# main.net
KiCad netlist of a schematic drawn in EAGLE
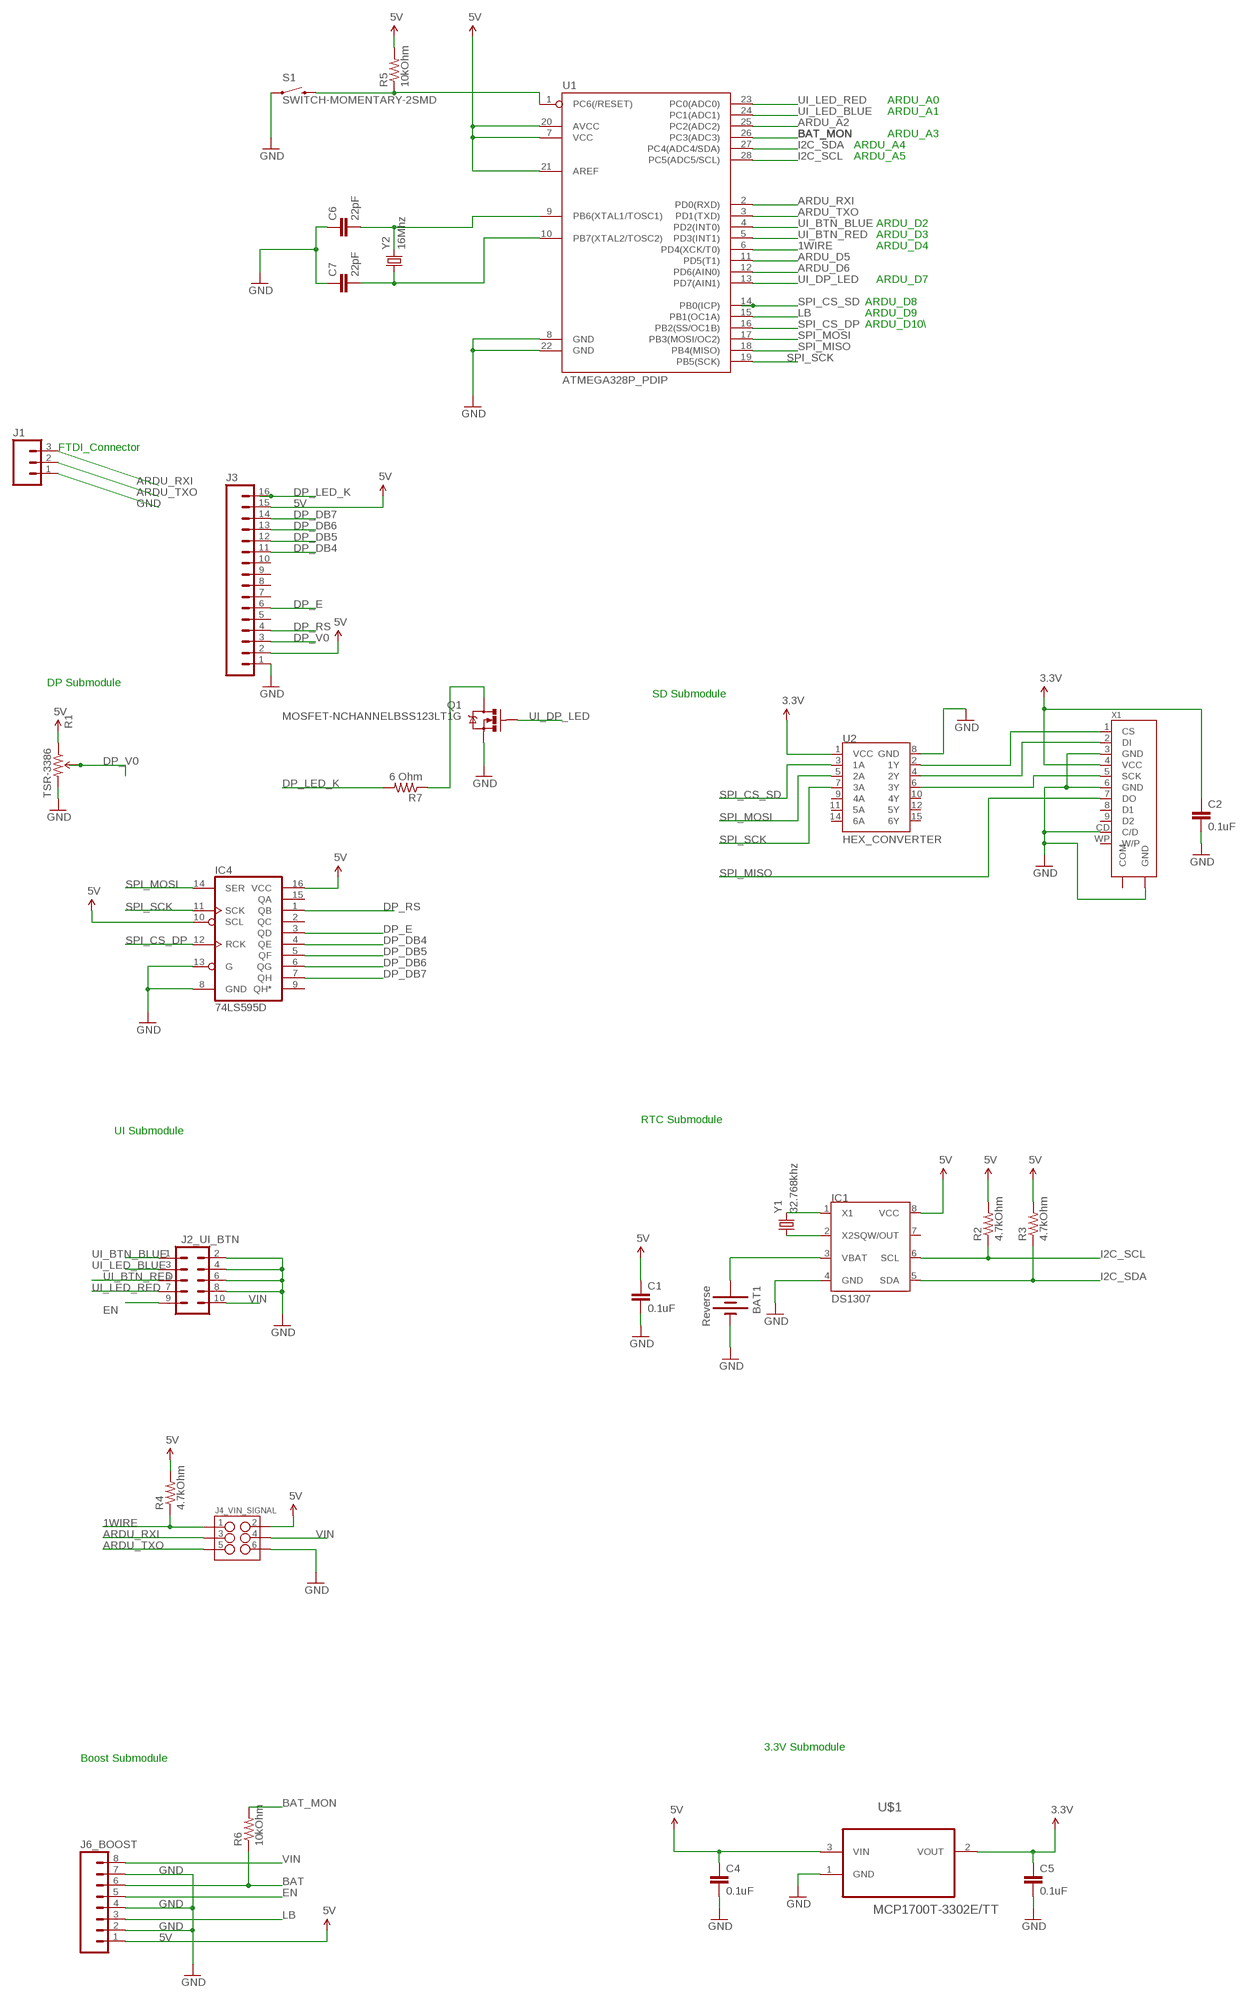
[diagram p0: schematic, sheet 1]

(export (version "E")
  (design (tool "Eeschema 10.0.6"))
  (components
    (comp (ref "BAT1")
      (value "Reverse")
      (footprint "eagle-import:BATTCOM_20MM_PTH")
      (libsource (lib "eagle-import") (part "BATTERY20PTH"))
    )
    (comp (ref "C1")
      (value "0.1uF")
      (footprint "eagle-import:1206")
      (libsource (lib "eagle-import") (part "CAP1206"))
    )
    (comp (ref "C2")
      (value "0.1uF")
      (footprint "eagle-import:1206")
      (libsource (lib "eagle-import") (part "CAP1206"))
    )
    (comp (ref "C4")
      (value "0.1uF")
      (footprint "eagle-import:1206")
      (libsource (lib "eagle-import") (part "CAP1206"))
    )
    (comp (ref "C5")
      (value "0.1uF")
      (footprint "eagle-import:1206")
      (libsource (lib "eagle-import") (part "CAP1206"))
    )
    (comp (ref "C6")
      (value "22pF")
      (footprint "eagle-import:1206")
      (libsource (lib "eagle-import") (part "CAP1206"))
    )
    (comp (ref "C7")
      (value "22pF")
      (footprint "eagle-import:1206")
      (libsource (lib "eagle-import") (part "CAP1206"))
    )
    (comp (ref "IC1")
      (value "DS1307")
      (footprint "eagle-import:SOIC-8")
      (libsource (lib "eagle-import") (part "DS1307"))
    )
    (comp (ref "IC4")
      (value "74LS595D")
      (footprint "eagle-import:SO16")
      (libsource (lib "eagle-import") (part "74595DLS"))
    )
    (comp (ref "J1")
      (value "M03LOCK")
      (footprint "eagle-import:1X03_LOCK")
      (libsource (lib "eagle-import") (part "M03LOCK"))
    )
    (comp (ref "J2_UI_BTN")
      (value "M05X2SHD")
      (footprint "eagle-import:2X5-SHROUDED")
      (libsource (lib "eagle-import") (part "M05X2SHD"))
    )
    (comp (ref "J3")
      (value "M16PTH")
      (footprint "eagle-import:1X16")
      (libsource (lib "eagle-import") (part "M16PTH"))
    )
    (comp (ref "J4_VIN_SIGNAL")
      (value "M03X2SHROUD")
      (footprint "eagle-import:2X3-SHROUDED")
      (libsource (lib "eagle-import") (part "M03X2SHROUD"))
    )
    (comp (ref "J6_BOOST")
      (value "M08")
      (footprint "eagle-import:1X08_ROUND")
      (libsource (lib "eagle-import") (part "M08"))
    )
    (comp (ref "Q1")
      (value "MOSFET-NCHANNELBSS123LT1G")
      (footprint "eagle-import:SOT23-3")
      (libsource (lib "eagle-import") (part "MOSFET-NCHANNELBSS123LT1G"))
    )
    (comp (ref "R1")
      (value "TSR-3386")
      (footprint "eagle-import:3386U")
      (libsource (lib "eagle-import") (part "TRIMPOT-PTH-KNOB"))
    )
    (comp (ref "R2")
      (value "4.7kOhm")
      (footprint "eagle-import:1206")
      (libsource (lib "eagle-import") (part "RESISTOR1206"))
    )
    (comp (ref "R3")
      (value "4.7kOhm")
      (footprint "eagle-import:1206")
      (libsource (lib "eagle-import") (part "RESISTOR1206"))
    )
    (comp (ref "R4")
      (value "4.7kOhm")
      (footprint "eagle-import:1206")
      (libsource (lib "eagle-import") (part "RESISTOR1206"))
    )
    (comp (ref "R5")
      (value "10kOhm")
      (footprint "eagle-import:1206")
      (libsource (lib "eagle-import") (part "RESISTOR1206"))
    )
    (comp (ref "R6")
      (value "10kOhm")
      (footprint "eagle-import:1206")
      (libsource (lib "eagle-import") (part "RESISTOR1206"))
    )
    (comp (ref "R7")
      (value "6 Ohm")
      (footprint "eagle-import:1206")
      (libsource (lib "eagle-import") (part "RESISTOR1206"))
    )
    (comp (ref "S1")
      (value "SWITCH-MOMENTARY-2SMD")
      (footprint "eagle-import:TACTILE-SWITCH-SMD")
      (libsource (lib "eagle-import") (part "SWITCH-MOMENTARY-2SMD"))
    )
    (comp (ref "U$1")
      (value "MCP1700T-3302E/TT")
      (footprint "eagle-import:SOT95P237X112-3N")
      (libsource (lib "eagle-import") (part "MCP1700T-3302E/TT"))
    )
    (comp (ref "U1")
      (value "ATMEGA328P_PDIP")
      (footprint "eagle-import:DIL28-3")
      (libsource (lib "eagle-import") (part "ATMEGA328P_PDIP"))
    )
    (comp (ref "U2")
      (value "HEX_CONVERTER")
      (footprint "eagle-import:SO016")
      (libsource (lib "eagle-import") (part "HEX_CONVERTER"))
    )
    (comp (ref "X1")
      (value "SD-SOCKET-AVX")
      (footprint "eagle-import:SD-SOCKET-AVX")
      (libsource (lib "eagle-import") (part "SD-SOCKET-AVX"))
    )
    (comp (ref "Y1")
      (value "32.768khz")
      (footprint "eagle-import:CRYSTAL-32KHZ-SMD-MELF")
      (libsource (lib "eagle-import") (part "CRYSTAL32-SMD-MELF"))
    )
    (comp (ref "Y2")
      (value "16Mhz")
      (footprint "eagle-import:HC49US")
      (libsource (lib "eagle-import") (part "CRYSTALHC49US"))
    )
  )
  (nets
    (net (code "1") (name "/1WIRE") (class "Default")
      (node (ref "J4_VIN_SIGNAL") (pin "1") (pinfunction "1_1") (pintype "bidirectional"))
      (node (ref "R4") (pin "1") (pinfunction "1_1") (pintype "passive"))
      (node (ref "U1") (pin "6") (pinfunction "PD4(XCK/T0)_6") (pintype "bidirectional"))
    )
    (net (code "2") (name "/ARDU_A2") (class "Default")
      (node (ref "U1") (pin "25") (pinfunction "PC2(ADC2)_25") (pintype "bidirectional"))
    )
    (net (code "3") (name "/ARDU_D5") (class "Default")
      (node (ref "U1") (pin "11") (pinfunction "PD5(T1)_11") (pintype "bidirectional"))
    )
    (net (code "4") (name "/ARDU_D6") (class "Default")
      (node (ref "U1") (pin "12") (pinfunction "PD6(AIN0)_12") (pintype "bidirectional"))
    )
    (net (code "5") (name "/ARDU_RXI") (class "Default")
      (node (ref "J1") (pin "3") (pinfunction "3_3") (pintype "passive"))
      (node (ref "J4_VIN_SIGNAL") (pin "3") (pinfunction "3_3") (pintype "bidirectional"))
      (node (ref "U1") (pin "2") (pinfunction "PD0(RXD)_2") (pintype "bidirectional"))
    )
    (net (code "6") (name "/ARDU_TXO") (class "Default")
      (node (ref "J1") (pin "2") (pinfunction "2_2") (pintype "passive"))
      (node (ref "J4_VIN_SIGNAL") (pin "5") (pinfunction "5_5") (pintype "bidirectional"))
      (node (ref "U1") (pin "3") (pinfunction "PD1(TXD)_3") (pintype "bidirectional"))
    )
    (net (code "7") (name "/BAT") (class "Default")
      (node (ref "J6_BOOST") (pin "6") (pinfunction "6_6") (pintype "passive"))
      (node (ref "R6") (pin "1") (pinfunction "1_1") (pintype "passive"))
    )
    (net (code "8") (name "/BAT_MON") (class "Default")
      (node (ref "R6") (pin "2") (pinfunction "2_2") (pintype "passive"))
      (node (ref "U1") (pin "26") (pinfunction "PC3(ADC3)_26") (pintype "bidirectional"))
    )
    (net (code "9") (name "/DP_DB4") (class "Default")
      (node (ref "IC4") (pin "4") (pinfunction "QE_4") (pintype "tri_state"))
      (node (ref "J3") (pin "11") (pinfunction "11_11") (pintype "passive"))
    )
    (net (code "10") (name "/DP_DB5") (class "Default")
      (node (ref "IC4") (pin "5") (pinfunction "QF_5") (pintype "tri_state"))
      (node (ref "J3") (pin "12") (pinfunction "12_12") (pintype "passive"))
    )
    (net (code "11") (name "/DP_DB6") (class "Default")
      (node (ref "IC4") (pin "6") (pinfunction "QG_6") (pintype "tri_state"))
      (node (ref "J3") (pin "13") (pinfunction "13_13") (pintype "passive"))
    )
    (net (code "12") (name "/DP_DB7") (class "Default")
      (node (ref "IC4") (pin "7") (pinfunction "QH_7") (pintype "tri_state"))
      (node (ref "J3") (pin "14") (pinfunction "14_14") (pintype "passive"))
    )
    (net (code "13") (name "/DP_E") (class "Default")
      (node (ref "IC4") (pin "3") (pinfunction "QD_3") (pintype "tri_state"))
      (node (ref "J3") (pin "6") (pinfunction "6_6") (pintype "passive"))
    )
    (net (code "14") (name "/DP_LED_K") (class "Default")
      (node (ref "J3") (pin "16") (pinfunction "16_16") (pintype "passive"))
      (node (ref "R7") (pin "2") (pinfunction "2_2") (pintype "passive"))
    )
    (net (code "15") (name "/DP_RS") (class "Default")
      (node (ref "IC4") (pin "1") (pinfunction "QB_1") (pintype "tri_state"))
      (node (ref "J3") (pin "4") (pinfunction "4_4") (pintype "passive"))
    )
    (net (code "16") (name "/DP_V0") (class "Default")
      (node (ref "J3") (pin "3") (pinfunction "3_3") (pintype "passive"))
      (node (ref "R1") (pin "2") (pinfunction "WIPER_2") (pintype "passive"))
    )
    (net (code "17") (name "/EN") (class "Default")
      (node (ref "J2_UI_BTN") (pin "9") (pinfunction "9_9") (pintype "passive"))
      (node (ref "J6_BOOST") (pin "5") (pinfunction "5_5") (pintype "passive"))
    )
    (net (code "18") (name "/I2C_SCL") (class "Default")
      (node (ref "IC1") (pin "6") (pinfunction "SCL_6") (pintype "input"))
      (node (ref "R2") (pin "1") (pinfunction "1_1") (pintype "passive"))
      (node (ref "U1") (pin "28") (pinfunction "PC5(ADC5/SCL)_28") (pintype "bidirectional"))
    )
    (net (code "19") (name "/I2C_SDA") (class "Default")
      (node (ref "IC1") (pin "5") (pinfunction "SDA_5") (pintype "bidirectional"))
      (node (ref "R3") (pin "1") (pinfunction "1_1") (pintype "passive"))
      (node (ref "U1") (pin "27") (pinfunction "PC4(ADC4/SDA)_27") (pintype "bidirectional"))
    )
    (net (code "20") (name "/LB") (class "Default")
      (node (ref "J6_BOOST") (pin "3") (pinfunction "3_3") (pintype "passive"))
      (node (ref "U1") (pin "15") (pinfunction "PB1(OC1A)_15") (pintype "bidirectional"))
    )
    (net (code "21") (name "/SPI_CS_DP") (class "Default")
      (node (ref "IC4") (pin "12") (pinfunction "RCK_12") (pintype "input"))
      (node (ref "U1") (pin "16") (pinfunction "PB2(SS/OC1B)_16") (pintype "bidirectional"))
    )
    (net (code "22") (name "/SPI_CS_SD") (class "Default")
      (node (ref "U1") (pin "14") (pinfunction "PB0(ICP)_14") (pintype "bidirectional"))
      (node (ref "U2") (pin "3") (pinfunction "1A_3") (pintype "bidirectional"))
    )
    (net (code "23") (name "/SPI_MISO") (class "Default")
      (node (ref "U1") (pin "18") (pinfunction "PB4(MISO)_18") (pintype "bidirectional"))
      (node (ref "X1") (pin "7") (pinfunction "DO_7") (pintype "bidirectional"))
    )
    (net (code "24") (name "/SPI_MOSI") (class "Default")
      (node (ref "IC4") (pin "14") (pinfunction "SER_14") (pintype "input"))
      (node (ref "U1") (pin "17") (pinfunction "PB3(MOSI/OC2)_17") (pintype "bidirectional"))
      (node (ref "U2") (pin "5") (pinfunction "2A_5") (pintype "bidirectional"))
    )
    (net (code "25") (name "/SPI_SCK") (class "Default")
      (node (ref "IC4") (pin "11") (pinfunction "SCK_11") (pintype "input"))
      (node (ref "U1") (pin "19") (pinfunction "PB5(SCK)_19") (pintype "bidirectional"))
      (node (ref "U2") (pin "7") (pinfunction "3A_7") (pintype "bidirectional"))
    )
    (net (code "26") (name "/UI_BTN_BLUE") (class "Default")
      (node (ref "J2_UI_BTN") (pin "1") (pinfunction "1_1") (pintype "passive"))
      (node (ref "U1") (pin "4") (pinfunction "PD2(INT0)_4") (pintype "bidirectional"))
    )
    (net (code "27") (name "/UI_BTN_RED") (class "Default")
      (node (ref "J2_UI_BTN") (pin "5") (pinfunction "5_5") (pintype "passive"))
      (node (ref "U1") (pin "5") (pinfunction "PD3(INT1)_5") (pintype "bidirectional"))
    )
    (net (code "28") (name "/UI_DP_LED") (class "Default")
      (node (ref "Q1") (pin "1") (pinfunction "G_1") (pintype "passive"))
      (node (ref "U1") (pin "13") (pinfunction "PD7(AIN1)_13") (pintype "bidirectional"))
    )
    (net (code "29") (name "/UI_LED_BLUE") (class "Default")
      (node (ref "J2_UI_BTN") (pin "3") (pinfunction "3_3") (pintype "passive"))
      (node (ref "U1") (pin "24") (pinfunction "PC1(ADC1)_24") (pintype "bidirectional"))
    )
    (net (code "30") (name "/UI_LED_RED") (class "Default")
      (node (ref "J2_UI_BTN") (pin "7") (pinfunction "7_7") (pintype "passive"))
      (node (ref "U1") (pin "23") (pinfunction "PC0(ADC0)_23") (pintype "bidirectional"))
    )
    (net (code "31") (name "/VIN") (class "Default")
      (node (ref "J2_UI_BTN") (pin "10") (pinfunction "10_10") (pintype "passive"))
      (node (ref "J4_VIN_SIGNAL") (pin "4") (pinfunction "4_4") (pintype "bidirectional"))
      (node (ref "J6_BOOST") (pin "8") (pinfunction "8_8") (pintype "passive"))
    )
    (net (code "32") (name "3.3V") (class "Default")
      (node (ref "C2") (pin "1") (pinfunction "1_1") (pintype "passive"))
      (node (ref "C5") (pin "1") (pinfunction "1_1") (pintype "passive"))
      (node (ref "U$1") (pin "2") (pinfunction "VOUT_2") (pintype "output"))
      (node (ref "U2") (pin "1") (pinfunction "VCC_1") (pintype "bidirectional"))
      (node (ref "X1") (pin "4") (pinfunction "VCC_4") (pintype "bidirectional"))
    )
    (net (code "33") (name "5V") (class "Default")
      (node (ref "C1") (pin "1") (pinfunction "1_1") (pintype "passive"))
      (node (ref "C4") (pin "1") (pinfunction "1_1") (pintype "passive"))
      (node (ref "IC1") (pin "8") (pinfunction "VCC_8") (pintype "power_in"))
      (node (ref "IC4") (pin "10") (pinfunction "SCL_10") (pintype "input"))
      (node (ref "IC4") (pin "16") (pinfunction "VCC_16") (pintype "power_in"))
      (node (ref "J3") (pin "15") (pinfunction "15_15") (pintype "passive"))
      (node (ref "J3") (pin "2") (pinfunction "2_2") (pintype "passive"))
      (node (ref "J4_VIN_SIGNAL") (pin "2") (pinfunction "2_2") (pintype "bidirectional"))
      (node (ref "J6_BOOST") (pin "1") (pinfunction "1_1") (pintype "passive"))
      (node (ref "R1") (pin "1") (pinfunction "CCW_1") (pintype "passive"))
      (node (ref "R2") (pin "2") (pinfunction "2_2") (pintype "passive"))
      (node (ref "R3") (pin "2") (pinfunction "2_2") (pintype "passive"))
      (node (ref "R4") (pin "2") (pinfunction "2_2") (pintype "passive"))
      (node (ref "R5") (pin "2") (pinfunction "2_2") (pintype "passive"))
      (node (ref "U$1") (pin "3") (pinfunction "VIN_3") (pintype "input"))
      (node (ref "U1") (pin "20") (pinfunction "AVCC_20") (pintype "bidirectional"))
      (node (ref "U1") (pin "21") (pinfunction "AREF_21") (pintype "bidirectional"))
      (node (ref "U1") (pin "7") (pinfunction "VCC_7") (pintype "bidirectional"))
    )
    (net (code "34") (name "GND") (class "Default")
      (node (ref "BAT1") (pin "2") (pinfunction "-_2") (pintype "power_in"))
      (node (ref "C1") (pin "2") (pinfunction "2_2") (pintype "passive"))
      (node (ref "C2") (pin "2") (pinfunction "2_2") (pintype "passive"))
      (node (ref "C4") (pin "2") (pinfunction "2_2") (pintype "passive"))
      (node (ref "C5") (pin "2") (pinfunction "2_2") (pintype "passive"))
      (node (ref "C6") (pin "1") (pinfunction "1_1") (pintype "passive"))
      (node (ref "C7") (pin "1") (pinfunction "1_1") (pintype "passive"))
      (node (ref "IC1") (pin "4") (pinfunction "GND_4") (pintype "power_in"))
      (node (ref "IC4") (pin "13") (pinfunction "G_13") (pintype "input"))
      (node (ref "IC4") (pin "8") (pinfunction "GND_8") (pintype "power_in"))
      (node (ref "J1") (pin "1") (pinfunction "1_1") (pintype "passive"))
      (node (ref "J2_UI_BTN") (pin "2") (pinfunction "2_2") (pintype "passive"))
      (node (ref "J2_UI_BTN") (pin "4") (pinfunction "4_4") (pintype "passive"))
      (node (ref "J2_UI_BTN") (pin "6") (pinfunction "6_6") (pintype "passive"))
      (node (ref "J2_UI_BTN") (pin "8") (pinfunction "8_8") (pintype "passive"))
      (node (ref "J3") (pin "1") (pinfunction "1_1") (pintype "passive"))
      (node (ref "J4_VIN_SIGNAL") (pin "6") (pinfunction "6_6") (pintype "bidirectional"))
      (node (ref "J6_BOOST") (pin "2") (pinfunction "2_2") (pintype "passive"))
      (node (ref "J6_BOOST") (pin "4") (pinfunction "4_4") (pintype "passive"))
      (node (ref "J6_BOOST") (pin "7") (pinfunction "7_7") (pintype "passive"))
      (node (ref "Q1") (pin "2") (pinfunction "S_2") (pintype "passive"))
      (node (ref "R1") (pin "3") (pinfunction "CW_3") (pintype "passive"))
      (node (ref "S1") (pin "1") (pinfunction "1_1") (pintype "passive"))
      (node (ref "U$1") (pin "1") (pinfunction "GND_1") (pintype "passive"))
      (node (ref "U1") (pin "22") (pinfunction "GND_22") (pintype "bidirectional"))
      (node (ref "U1") (pin "8") (pinfunction "GND_8") (pintype "bidirectional"))
      (node (ref "U2") (pin "8") (pinfunction "GND_8") (pintype "bidirectional"))
      (node (ref "X1") (pin "3") (pinfunction "GND_3") (pintype "bidirectional"))
      (node (ref "X1") (pin "6") (pinfunction "GND_6") (pintype "bidirectional"))
      (node (ref "X1") (pin "CD") (pinfunction "C/D_CD") (pintype "bidirectional"))
      (node (ref "X1") (pin "GND@2") (pinfunction "GND_GND@2") (pintype "bidirectional"))
    )
    (net (code "35") (name "Net-(BAT1-+)") (class "Default")
      (node (ref "BAT1") (pin "1") (pinfunction "+_1") (pintype "power_in"))
      (node (ref "IC1") (pin "3") (pinfunction "VBAT_3") (pintype "power_in"))
    )
    (net (code "36") (name "Net-(IC1-X1)") (class "Default")
      (node (ref "IC1") (pin "1") (pinfunction "X1_1") (pintype "input"))
      (node (ref "Y1") (pin "X2") (pinfunction "2_X2") (pintype "passive"))
    )
    (net (code "37") (name "Net-(IC1-X2)") (class "Default")
      (node (ref "IC1") (pin "2") (pinfunction "X2_2") (pintype "output"))
      (node (ref "Y1") (pin "X1") (pinfunction "1_X1") (pintype "passive"))
    )
    (net (code "38") (name "Net-(Q1-D)") (class "Default")
      (node (ref "Q1") (pin "3") (pinfunction "D_3") (pintype "passive"))
      (node (ref "R7") (pin "1") (pinfunction "1_1") (pintype "passive"))
    )
    (net (code "39") (name "Net-(S1-2)") (class "Default")
      (node (ref "R5") (pin "1") (pinfunction "1_1") (pintype "passive"))
      (node (ref "S1") (pin "3") (pinfunction "2_3") (pintype "passive"))
      (node (ref "U1") (pin "1") (pinfunction "PC6(/RESET)_1") (pintype "bidirectional"))
    )
    (net (code "40") (name "Net-(U1-PB6(XTAL1{slash}TOSC1))") (class "Default")
      (node (ref "C6") (pin "2") (pinfunction "2_2") (pintype "passive"))
      (node (ref "U1") (pin "9") (pinfunction "PB6(XTAL1/TOSC1)_9") (pintype "bidirectional"))
      (node (ref "Y2") (pin "2") (pinfunction "2_2") (pintype "passive"))
    )
    (net (code "41") (name "Net-(U1-PB7(XTAL2{slash}TOSC2))") (class "Default")
      (node (ref "C7") (pin "2") (pinfunction "2_2") (pintype "passive"))
      (node (ref "U1") (pin "10") (pinfunction "PB7(XTAL2/TOSC2)_10") (pintype "bidirectional"))
      (node (ref "Y2") (pin "1") (pinfunction "1_1") (pintype "passive"))
    )
    (net (code "42") (name "Net-(U2-1Y)") (class "Default")
      (node (ref "U2") (pin "2") (pinfunction "1Y_2") (pintype "bidirectional"))
      (node (ref "X1") (pin "1") (pinfunction "CS_1") (pintype "bidirectional"))
    )
    (net (code "43") (name "Net-(U2-2Y)") (class "Default")
      (node (ref "U2") (pin "4") (pinfunction "2Y_4") (pintype "bidirectional"))
      (node (ref "X1") (pin "2") (pinfunction "DI_2") (pintype "bidirectional"))
    )
    (net (code "44") (name "Net-(U2-3Y)") (class "Default")
      (node (ref "U2") (pin "6") (pinfunction "3Y_6") (pintype "bidirectional"))
      (node (ref "X1") (pin "5") (pinfunction "SCK_5") (pintype "bidirectional"))
    )
    (net (code "45") (name "unconnected-(IC1-SQW{slash}OUT-Pad7)") (class "Default")
      (node (ref "IC1") (pin "7") (pinfunction "SQW/OUT_7") (pintype "output"))
    )
    (net (code "46") (name "unconnected-(IC4-QA-Pad15)") (class "Default")
      (node (ref "IC4") (pin "15") (pinfunction "QA_15") (pintype "tri_state"))
    )
    (net (code "47") (name "unconnected-(IC4-QC-Pad2)") (class "Default")
      (node (ref "IC4") (pin "2") (pinfunction "QC_2") (pintype "tri_state"))
    )
    (net (code "48") (name "unconnected-(IC4-QH*-Pad9)") (class "Default")
      (node (ref "IC4") (pin "9") (pinfunction "QH*_9") (pintype "tri_state"))
    )
    (net (code "49") (name "unconnected-(J3-Pad5)") (class "Default")
      (node (ref "J3") (pin "5") (pinfunction "5_5") (pintype "passive"))
    )
    (net (code "50") (name "unconnected-(J3-Pad7)") (class "Default")
      (node (ref "J3") (pin "7") (pinfunction "7_7") (pintype "passive"))
    )
    (net (code "51") (name "unconnected-(J3-Pad8)") (class "Default")
      (node (ref "J3") (pin "8") (pinfunction "8_8") (pintype "passive"))
    )
    (net (code "52") (name "unconnected-(J3-Pad9)") (class "Default")
      (node (ref "J3") (pin "9") (pinfunction "9_9") (pintype "passive"))
    )
    (net (code "53") (name "unconnected-(J3-Pad10)") (class "Default")
      (node (ref "J3") (pin "10") (pinfunction "10_10") (pintype "passive"))
    )
    (net (code "54") (name "unconnected-(U2-4A-Pad9)") (class "Default")
      (node (ref "U2") (pin "9") (pinfunction "4A_9") (pintype "bidirectional"))
    )
    (net (code "55") (name "unconnected-(U2-4Y-Pad10)") (class "Default")
      (node (ref "U2") (pin "10") (pinfunction "4Y_10") (pintype "bidirectional"))
    )
    (net (code "56") (name "unconnected-(U2-5A-Pad11)") (class "Default")
      (node (ref "U2") (pin "11") (pinfunction "5A_11") (pintype "bidirectional"))
    )
    (net (code "57") (name "unconnected-(U2-5Y-Pad12)") (class "Default")
      (node (ref "U2") (pin "12") (pinfunction "5Y_12") (pintype "bidirectional"))
    )
    (net (code "58") (name "unconnected-(U2-6A-Pad14)") (class "Default")
      (node (ref "U2") (pin "14") (pinfunction "6A_14") (pintype "bidirectional"))
    )
    (net (code "59") (name "unconnected-(U2-6Y-Pad15)") (class "Default")
      (node (ref "U2") (pin "15") (pinfunction "6Y_15") (pintype "bidirectional"))
    )
    (net (code "60") (name "unconnected-(X1-D1-Pad8)") (class "Default")
      (node (ref "X1") (pin "8") (pinfunction "D1_8") (pintype "bidirectional"))
    )
    (net (code "61") (name "unconnected-(X1-D2-Pad9)") (class "Default")
      (node (ref "X1") (pin "9") (pinfunction "D2_9") (pintype "bidirectional"))
    )
    (net (code "62") (name "unconnected-(X1-PadCOM)") (class "Default")
      (node (ref "X1") (pin "COM") (pinfunction "COM_COM") (pintype "bidirectional"))
    )
    (net (code "63") (name "unconnected-(X1-W{slash}P-PadWP)") (class "Default")
      (node (ref "X1") (pin "WP") (pinfunction "W/P_WP") (pintype "bidirectional"))
    )
  )
)
